# USB_OTG_FS.net
KiCad netlist of a schematic drawn in Altium Designer
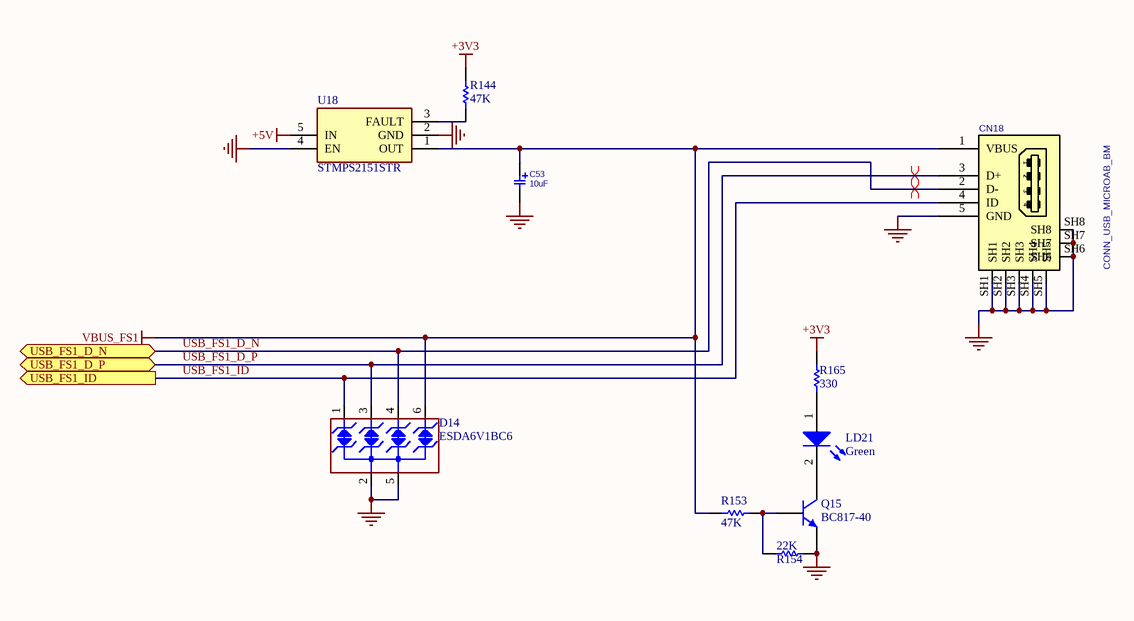
[diagram p0: USB_OTG_FS.SchDoc]

(export (version "E")
  (design (tool "Eeschema 10.0.6"))
  (components
    (comp (ref "C53")
      (value "10uF")
      (footprint "C_TN_3216")
      (description "CAP, SMD, TAN")
      (fields (field (name "MANF") "VISHAY") (field (name "MANF_P#") "T55A106M6R3C0300"))
      (libsource (lib "CapTantal_passive") (part "CAP_SMD_TAN_10uF_6.3V"))
    )
    (comp (ref "CN18")
      (value "CONN_USB_MICROAB_BM")
      (footprint "USB_MICRO_AB_BM_SHT")
      (description "CONN, USB, MICRO AB, R/A, SMD, BOTTOM MOUNT")
      (fields (field (name "MANF_P#") "47589-0001") (field (name "MANF") "MOLEX"))
      (libsource (lib "conn_usb") (part "CONN_USB_MICRO_AB_BM_SHT"))
    )
    (comp (ref "D14")
      (value "ESDA6V1BC6")
      (footprint "samacsys:SOT95P280X145-6N")
      (description "4-line ESD protection")
      (libsource (lib "MB1137") (part "ESDA6V1BC6"))
    )
    (comp (ref "LD21")
      (value "Green")
      (footprint "LED0603GRN")
      (description "Typical RED, GREEN, YELLOW, AMBER GaAs LED")
      (fields (field (name "PUBLISHER") "Altium Limited"))
      (libsource (lib "Miscellaneous Devices") (part "LED2"))
    )
    (comp (ref "Q15")
      (value "BC817-40")
      (footprint "SOT-23-3")
      (description "TRANS NPN 300V 0.3A SOT23")
      (fields
        (field (name "PART NUMBER") "BC817-40")
        (field (name "MANUFACTURER") "Micro Commercial Co")
        (field (name "BASE PART NUMBER") "MMBTA42")
      )
      (libsource (lib "Main_Lib") (part "BC817-40"))
    )
    (comp (ref "R144")
      (value "47K")
      (footprint "R0603E")
      (description "Resistor")
      (fields (field (name "PUBLISHER") "Altium Limited"))
      (libsource (lib "Miscellaneous Devices") (part "res1"))
    )
    (comp (ref "R153")
      (value "47K")
      (footprint "R0603E")
      (description "Resistor")
      (fields (field (name "PUBLISHER") "Altium Limited"))
      (libsource (lib "Miscellaneous Devices") (part "res1"))
    )
    (comp (ref "R154")
      (value "22K")
      (footprint "R0603E")
      (description "Resistor")
      (fields (field (name "PUBLISHER") "Altium Limited"))
      (libsource (lib "Miscellaneous Devices") (part "res1"))
    )
    (comp (ref "R165")
      (value "330")
      (footprint "R0603E")
      (description "Resistor")
      (fields (field (name "PUBLISHER") "Altium Limited"))
      (libsource (lib "Miscellaneous Devices") (part "res1"))
    )
    (comp (ref "U18")
      (value "STMPS2151STR")
      (footprint "SamacSys:SOT95P280X145-5N")
      (description "Integrated Circuit")
      (libsource (lib "*") (part "STMPS2151STR"))
    )
  )
  (nets
    (net (code "1") (name "+3V3") (class "Default")
      (node (ref "R144") (pin "1") (pinfunction "1_1") (pintype "passive"))
      (node (ref "R165") (pin "2") (pinfunction "2_2") (pintype "passive"))
    )
    (net (code "2") (name "+5V") (class "Default")
      (node (ref "U18") (pin "5") (pinfunction "IN_5") (pintype "passive"))
    )
    (net (code "3") (name "/USB_FS1_D_N") (class "Default")
      (node (ref "CN18") (pin "2") (pinfunction "D-_2") (pintype "passive"))
      (node (ref "D14") (pin "4") (pinfunction "IO3_4") (pintype "passive"))
    )
    (net (code "4") (name "/USB_FS1_D_P") (class "Default")
      (node (ref "CN18") (pin "3") (pinfunction "D+_3") (pintype "passive"))
      (node (ref "D14") (pin "3") (pinfunction "GND_3") (pintype "passive"))
    )
    (net (code "5") (name "/USB_FS1_ID") (class "Default")
      (node (ref "CN18") (pin "4") (pinfunction "ID_4") (pintype "power_in"))
      (node (ref "D14") (pin "1") (pinfunction "IO1_1") (pintype "passive"))
    )
    (net (code "6") (name "GND") (class "Default")
      (node (ref "C53") (pin "2") (pinfunction "2_2") (pintype "passive"))
      (node (ref "CN18") (pin "5") (pinfunction "GND_5") (pintype "power_in"))
      (node (ref "CN18") (pin "SH1") (pinfunction "SH1_SH1") (pintype "passive"))
      (node (ref "CN18") (pin "SH2") (pinfunction "SH2_SH2") (pintype "passive"))
      (node (ref "CN18") (pin "SH3") (pinfunction "SH3_SH3") (pintype "passive"))
      (node (ref "CN18") (pin "SH4") (pinfunction "SH4_SH4") (pintype "passive"))
      (node (ref "CN18") (pin "SH5") (pinfunction "SH5_SH5") (pintype "passive"))
      (node (ref "CN18") (pin "SH6") (pinfunction "SH6_SH6") (pintype "passive"))
      (node (ref "CN18") (pin "SH7") (pinfunction "SH7_SH7") (pintype "passive"))
      (node (ref "CN18") (pin "SH8") (pinfunction "SH8_SH8") (pintype "passive"))
      (node (ref "D14") (pin "2") (pinfunction "IO2_2") (pintype "passive"))
      (node (ref "D14") (pin "5") (pinfunction "IO4_5") (pintype "passive"))
      (node (ref "Q15") (pin "2") (pinfunction "E_2") (pintype "passive"))
      (node (ref "R154") (pin "1") (pinfunction "1_1") (pintype "passive"))
      (node (ref "U18") (pin "2") (pinfunction "GND_2") (pintype "passive"))
      (node (ref "U18") (pin "4") (pinfunction "EN_4") (pintype "passive"))
    )
    (net (code "7") (name "Net-(LD21-A)") (class "Default")
      (node (ref "LD21") (pin "1") (pinfunction "A_1") (pintype "passive"))
      (node (ref "R165") (pin "1") (pinfunction "1_1") (pintype "passive"))
    )
    (net (code "8") (name "Net-(LD21-K)") (class "Default")
      (node (ref "LD21") (pin "2") (pinfunction "K_2") (pintype "passive"))
      (node (ref "Q15") (pin "3") (pinfunction "C_3") (pintype "passive"))
    )
    (net (code "9") (name "Net-(Q15-B)") (class "Default")
      (node (ref "Q15") (pin "1") (pinfunction "B_1") (pintype "passive"))
      (node (ref "R153") (pin "2") (pinfunction "2_2") (pintype "passive"))
      (node (ref "R154") (pin "2") (pinfunction "2_2") (pintype "passive"))
    )
    (net (code "10") (name "Net-(U18-FAULT)") (class "Default")
      (node (ref "R144") (pin "2") (pinfunction "2_2") (pintype "passive"))
      (node (ref "U18") (pin "3") (pinfunction "FAULT_3") (pintype "passive"))
    )
    (net (code "11") (name "VBUS_FS1") (class "Default")
      (node (ref "C53") (pin "1") (pinfunction "1_1") (pintype "passive"))
      (node (ref "CN18") (pin "1") (pinfunction "VBUS_1") (pintype "power_in"))
      (node (ref "D14") (pin "6") (pinfunction "NC_6") (pintype "passive"))
      (node (ref "R153") (pin "1") (pinfunction "1_1") (pintype "passive"))
      (node (ref "U18") (pin "1") (pinfunction "OUT_1") (pintype "passive"))
    )
  )
)
